# Acoustic_Signal_Localization_Schematic.net
KiCad netlist of a schematic drawn in Altium Designer
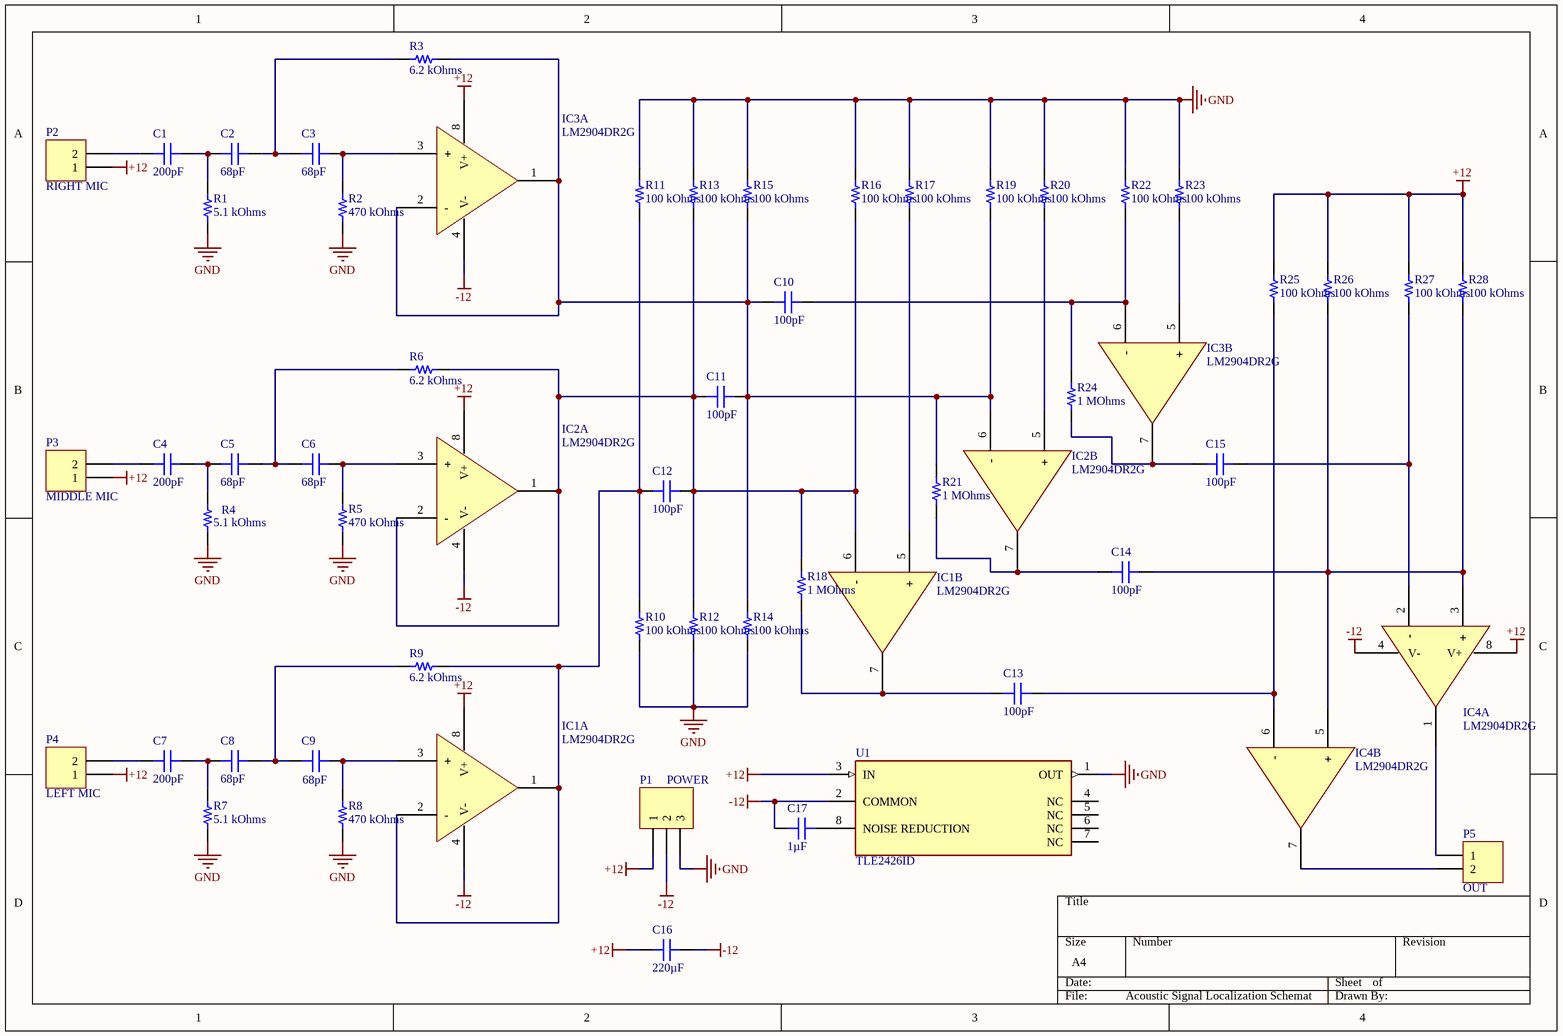
[diagram p0: Acoustic Signal Localization Schematic.SchDoc]

(export (version "E")
  (design (tool "Eeschema 10.0.6"))
  (components
    (comp (ref "C1")
      (value "200pF")
      (footprint "CAP 1210_3225 - 1.6MM")
      (description "CAP CER 1210 200PF 630V C0G 5% F")
      (fields (field (name "PART NUMBER") "C1210X201JBGACAUTO") (field (name "MANUFACTURER") "KEMET"))
      (libsource (lib "Celestial Altium Library - altium_library") (part "Capacitor"))
    )
    (comp (ref "C2")
      (value "68pF")
      (footprint "CAP 1210_3225 - 1.6MM")
      (description "CAP CER 680PF 2KV X7R 1210")
      (fields (field (name "PART NUMBER") "C1210C681KGRACTU") (field (name "MANUFACTURER") "KEMET"))
      (libsource (lib "Celestial Altium Library - altium_library") (part "Capacitor"))
    )
    (comp (ref "C3")
      (value "68pF")
      (footprint "CAP 1210_3225 - 1.6MM")
      (description "CAP CER 680PF 2KV X7R 1210")
      (fields (field (name "PART NUMBER") "C1210C681KGRACTU") (field (name "MANUFACTURER") "KEMET"))
      (libsource (lib "Celestial Altium Library - altium_library") (part "Capacitor"))
    )
    (comp (ref "C4")
      (value "200pF")
      (footprint "CAP 1210_3225 - 1.6MM")
      (description "CAP CER 1210 200PF 630V C0G 5% F")
      (fields (field (name "PART NUMBER") "C1210X201JBGACAUTO") (field (name "MANUFACTURER") "KEMET"))
      (libsource (lib "Celestial Altium Library - altium_library") (part "Capacitor"))
    )
    (comp (ref "C5")
      (value "68pF")
      (footprint "CAP 1210_3225 - 1.6MM")
      (description "CAP CER 680PF 2KV X7R 1210")
      (fields (field (name "PART NUMBER") "C1210C681KGRACTU") (field (name "MANUFACTURER") "KEMET"))
      (libsource (lib "Celestial Altium Library - altium_library") (part "Capacitor"))
    )
    (comp (ref "C6")
      (value "68pF")
      (footprint "CAP 1210_3225 - 1.6MM")
      (description "CAP CER 680PF 2KV X7R 1210")
      (fields (field (name "PART NUMBER") "C1210C681KGRACTU") (field (name "MANUFACTURER") "KEMET"))
      (libsource (lib "Celestial Altium Library - altium_library") (part "Capacitor"))
    )
    (comp (ref "C7")
      (value "200pF")
      (footprint "CAP 1210_3225 - 1.6MM")
      (description "CAP CER 1210 200PF 630V C0G 5% F")
      (fields (field (name "PART NUMBER") "C1210X201JBGACAUTO") (field (name "MANUFACTURER") "KEMET"))
      (libsource (lib "Celestial Altium Library - altium_library") (part "Capacitor"))
    )
    (comp (ref "C8")
      (value "68pF")
      (footprint "CAP 1210_3225 - 1.6MM")
      (description "CAP CER 680PF 2KV X7R 1210")
      (fields (field (name "PART NUMBER") "C1210C681KGRACTU") (field (name "MANUFACTURER") "KEMET"))
      (libsource (lib "Celestial Altium Library - altium_library") (part "Capacitor"))
    )
    (comp (ref "C9")
      (value "68pF")
      (footprint "CAP 1210_3225 - 1.6MM")
      (description "CAP CER 680PF 2KV X7R 1210")
      (fields (field (name "PART NUMBER") "C1210C681KGRACTU") (field (name "MANUFACTURER") "KEMET"))
      (libsource (lib "Celestial Altium Library - altium_library") (part "Capacitor"))
    )
    (comp (ref "C10")
      (value "100pF")
      (footprint "CAP 1210_3225 - 1.8MM")
      (description "CAP CER 100PF 1KV C0G/NP0 1210")
      (fields
        (field (name "PART NUMBER") "VJ1210A101JXGAT5Z")
        (field (name "MANUFACTURER") "Vishay Vitramon")
      )
      (libsource (lib "Celestial Altium Library - altium_library") (part "Capacitor"))
    )
    (comp (ref "C11")
      (value "100pF")
      (footprint "CAP 1210_3225 - 1.8MM")
      (description "CAP CER 100PF 1KV C0G/NP0 1210")
      (fields
        (field (name "PART NUMBER") "VJ1210A101JXGAT5Z")
        (field (name "MANUFACTURER") "Vishay Vitramon")
      )
      (libsource (lib "Celestial Altium Library - altium_library") (part "Capacitor"))
    )
    (comp (ref "C12")
      (value "100pF")
      (footprint "CAP 1210_3225 - 1.8MM")
      (description "CAP CER 100PF 1KV C0G/NP0 1210")
      (fields
        (field (name "PART NUMBER") "VJ1210A101JXGAT5Z")
        (field (name "MANUFACTURER") "Vishay Vitramon")
      )
      (libsource (lib "Celestial Altium Library - altium_library") (part "Capacitor"))
    )
    (comp (ref "C13")
      (value "100pF")
      (footprint "CAP 1210_3225 - 1.8MM")
      (description "CAP CER 100PF 1KV C0G/NP0 1210")
      (fields
        (field (name "PART NUMBER") "VJ1210A101JXGAT5Z")
        (field (name "MANUFACTURER") "Vishay Vitramon")
      )
      (libsource (lib "Celestial Altium Library - altium_library") (part "Capacitor"))
    )
    (comp (ref "C14")
      (value "100pF")
      (footprint "CAP 1210_3225 - 1.8MM")
      (description "CAP CER 100PF 1KV C0G/NP0 1210")
      (fields
        (field (name "PART NUMBER") "VJ1210A101JXGAT5Z")
        (field (name "MANUFACTURER") "Vishay Vitramon")
      )
      (libsource (lib "Celestial Altium Library - altium_library") (part "Capacitor"))
    )
    (comp (ref "C15")
      (value "100pF")
      (footprint "CAP 1210_3225 - 1.8MM")
      (description "CAP CER 100PF 1KV C0G/NP0 1210")
      (fields
        (field (name "PART NUMBER") "VJ1210A101JXGAT5Z")
        (field (name "MANUFACTURER") "Vishay Vitramon")
      )
      (libsource (lib "Celestial Altium Library - altium_library") (part "Capacitor"))
    )
    (comp (ref "C16")
      (value "220µF")
      (footprint "CAP 1210_3225 - 2.8MM")
      (description "CAP CER 220UF 2.5V X6S 1210")
      (fields
        (field (name "PART NUMBER") "GRM32EC80E227ME05L")
        (field (name "MANUFACTURER") "Murata Electronics")
      )
      (libsource (lib "Celestial Altium Library - altium_library") (part "Capacitor"))
    )
    (comp (ref "C17")
      (value "1µF")
      (footprint "CAP 1210_3225 - 2.8MM")
      (description "CAP CER 1UF 100V X7R 1210")
      (fields
        (field (name "PART NUMBER") "CL32B105KCJNNNE")
        (field (name "MANUFACTURER") "Samsung Electro-Mechanics")
      )
      (libsource (lib "Celestial Altium Library - altium_library") (part "Capacitor"))
    )
    (comp (ref "IC1")
      (value "LM2904DR2G")
      (footprint "TI SOIC-8 D")
      (description "IC OPAMP GP 2 CIRCUIT 8SOIC")
      (fields (field (name "MANUFACTURER") "ON Semiconductor"))
      (libsource (lib "Celestial Altium Library - altium_library") (part "TI LM2904DR"))
    )
    (comp (ref "IC2")
      (value "LM2904DR2G")
      (footprint "TI SOIC-8 D")
      (description "IC OPAMP GP 2 CIRCUIT 8SOIC")
      (fields (field (name "MANUFACTURER") "ON Semiconductor"))
      (libsource (lib "Celestial Altium Library - altium_library") (part "TI LM2904DR"))
    )
    (comp (ref "IC3")
      (value "LM2904DR2G")
      (footprint "TI SOIC-8 D")
      (description "IC OPAMP GP 2 CIRCUIT 8SOIC")
      (fields (field (name "MANUFACTURER") "ON Semiconductor"))
      (libsource (lib "Celestial Altium Library - altium_library") (part "TI LM2904DR"))
    )
    (comp (ref "IC4")
      (value "LM2904DR2G")
      (footprint "TI SOIC-8 D")
      (description "IC OPAMP GP 2 CIRCUIT 8SOIC")
      (fields (field (name "MANUFACTURER") "ON Semiconductor"))
      (libsource (lib "Celestial Altium Library - altium_library") (part "TI LM2904DR"))
    )
    (comp (ref "P1")
      (value "POWER")
      (footprint "HDR1X3")
      (description "Header, 3-Pin")
      (fields (field (name "PUBLISHER") "Altium Limited"))
      (libsource (lib "Miscellaneous Connectors") (part "Header 3"))
    )
    (comp (ref "P2")
      (value "RIGHT MIC")
      (footprint "HDR1X2")
      (description "Header, 2-Pin")
      (fields (field (name "PUBLISHER") "Altium Limited"))
      (libsource (lib "") (part "Header 2_1"))
    )
    (comp (ref "P3")
      (value "MIDDLE MIC")
      (footprint "HDR1X2")
      (description "Header, 2-Pin")
      (fields (field (name "PUBLISHER") "Altium Limited"))
      (libsource (lib "") (part "Header 2_1"))
    )
    (comp (ref "P4")
      (value "LEFT MIC")
      (footprint "HDR1X2")
      (description "Header, 2-Pin")
      (fields (field (name "PUBLISHER") "Altium Limited"))
      (libsource (lib "") (part "Header 2_1"))
    )
    (comp (ref "P5")
      (value "OUT")
      (footprint "HDR1X2")
      (description "Header, 2-Pin")
      (fields (field (name "PUBLISHER") "Altium Limited"))
      (libsource (lib "Miscellaneous Connectors") (part "Header 2"))
    )
    (comp (ref "R1")
      (value "5.1 kOhms")
      (footprint "RES 1210_3225")
      (description "RES 5.1K OHM 5% 1/2W 1210")
      (fields
        (field (name "PART NUMBER") "RK73B2ETTD512J")
        (field (name "MANUFACTURER") "KOA Speer Electronics, Inc.")
      )
      (libsource (lib "Celestial Altium Library - altium_library") (part "Resistor"))
    )
    (comp (ref "R2")
      (value "470 kOhms")
      (footprint "RES 1210_3225")
      (description "RES 470K OHM 5% 1/3W 1210")
      (fields
        (field (name "PART NUMBER") "RMCF1210JT470K")
        (field (name "MANUFACTURER") "Stackpole Electronics Inc")
      )
      (libsource (lib "Celestial Altium Library - altium_library") (part "Resistor"))
    )
    (comp (ref "R3")
      (value "6.2 kOhms")
      (footprint "RES 1210_3225")
      (description "RES 6.2K OHM 5% 1/2W 1210")
      (fields
        (field (name "PART NUMBER") "RK73B2ETTD622J")
        (field (name "MANUFACTURER") "KOA Speer Electronics, Inc.")
      )
      (libsource (lib "Celestial Altium Library - altium_library") (part "Resistor"))
    )
    (comp (ref "R4")
      (value "5.1 kOhms")
      (footprint "RES 1210_3225")
      (description "RES 5.1K OHM 5% 1/2W 1210")
      (fields
        (field (name "PART NUMBER") "RK73B2ETTD512J")
        (field (name "MANUFACTURER") "KOA Speer Electronics, Inc.")
      )
      (libsource (lib "Celestial Altium Library - altium_library") (part "Resistor"))
    )
    (comp (ref "R5")
      (value "470 kOhms")
      (footprint "RES 1210_3225")
      (description "RES 470K OHM 5% 1/3W 1210")
      (fields
        (field (name "PART NUMBER") "RMCF1210JT470K")
        (field (name "MANUFACTURER") "Stackpole Electronics Inc")
      )
      (libsource (lib "Celestial Altium Library - altium_library") (part "Resistor"))
    )
    (comp (ref "R6")
      (value "6.2 kOhms")
      (footprint "RES 1210_3225")
      (description "RES 6.2K OHM 5% 1/2W 1210")
      (fields
        (field (name "PART NUMBER") "RK73B2ETTD622J")
        (field (name "MANUFACTURER") "KOA Speer Electronics, Inc.")
      )
      (libsource (lib "Celestial Altium Library - altium_library") (part "Resistor"))
    )
    (comp (ref "R7")
      (value "5.1 kOhms")
      (footprint "RES 1210_3225")
      (description "RES 5.1K OHM 5% 1/2W 1210")
      (fields
        (field (name "PART NUMBER") "RK73B2ETTD512J")
        (field (name "MANUFACTURER") "KOA Speer Electronics, Inc.")
      )
      (libsource (lib "Celestial Altium Library - altium_library") (part "Resistor"))
    )
    (comp (ref "R8")
      (value "470 kOhms")
      (footprint "RES 1210_3225")
      (description "RES 470K OHM 5% 1/3W 1210")
      (fields
        (field (name "PART NUMBER") "RMCF1210JT470K")
        (field (name "MANUFACTURER") "Stackpole Electronics Inc")
      )
      (libsource (lib "Celestial Altium Library - altium_library") (part "Resistor"))
    )
    (comp (ref "R9")
      (value "6.2 kOhms")
      (footprint "RES 1210_3225")
      (description "RES 6.2K OHM 5% 1/2W 1210")
      (fields
        (field (name "PART NUMBER") "RK73B2ETTD622J")
        (field (name "MANUFACTURER") "KOA Speer Electronics, Inc.")
      )
      (libsource (lib "Celestial Altium Library - altium_library") (part "Resistor"))
    )
    (comp (ref "R10")
      (value "100 kOhms")
      (footprint "RES 1210_3225")
      (description "RES 100K OHM 1% 1/3W 1210")
      (fields
        (field (name "PART NUMBER") "RMCF1210FT100K")
        (field (name "MANUFACTURER") "Stackpole Electronics Inc")
      )
      (libsource (lib "Celestial Altium Library - altium_library") (part "Resistor"))
    )
    (comp (ref "R11")
      (value "100 kOhms")
      (footprint "RES 1210_3225")
      (description "RES 100K OHM 1% 1/3W 1210")
      (fields
        (field (name "PART NUMBER") "RMCF1210FT100K")
        (field (name "MANUFACTURER") "Stackpole Electronics Inc")
      )
      (libsource (lib "Celestial Altium Library - altium_library") (part "Resistor"))
    )
    (comp (ref "R12")
      (value "100 kOhms")
      (footprint "RES 1210_3225")
      (description "RES 100K OHM 1% 1/3W 1210")
      (fields
        (field (name "PART NUMBER") "RMCF1210FT100K")
        (field (name "MANUFACTURER") "Stackpole Electronics Inc")
      )
      (libsource (lib "Celestial Altium Library - altium_library") (part "Resistor"))
    )
    (comp (ref "R13")
      (value "100 kOhms")
      (footprint "RES 1210_3225")
      (description "RES 100K OHM 1% 1/3W 1210")
      (fields
        (field (name "PART NUMBER") "RMCF1210FT100K")
        (field (name "MANUFACTURER") "Stackpole Electronics Inc")
      )
      (libsource (lib "Celestial Altium Library - altium_library") (part "Resistor"))
    )
    (comp (ref "R14")
      (value "100 kOhms")
      (footprint "RES 1210_3225")
      (description "RES 100K OHM 1% 1/3W 1210")
      (fields
        (field (name "PART NUMBER") "RMCF1210FT100K")
        (field (name "MANUFACTURER") "Stackpole Electronics Inc")
      )
      (libsource (lib "Celestial Altium Library - altium_library") (part "Resistor"))
    )
    (comp (ref "R15")
      (value "100 kOhms")
      (footprint "RES 1210_3225")
      (description "RES 100K OHM 1% 1/3W 1210")
      (fields
        (field (name "PART NUMBER") "RMCF1210FT100K")
        (field (name "MANUFACTURER") "Stackpole Electronics Inc")
      )
      (libsource (lib "Celestial Altium Library - altium_library") (part "Resistor"))
    )
    (comp (ref "R16")
      (value "100 kOhms")
      (footprint "RES 1210_3225")
      (description "RES 100K OHM 1% 1/3W 1210")
      (fields
        (field (name "PART NUMBER") "RMCF1210FT100K")
        (field (name "MANUFACTURER") "Stackpole Electronics Inc")
      )
      (libsource (lib "Celestial Altium Library - altium_library") (part "Resistor"))
    )
    (comp (ref "R17")
      (value "100 kOhms")
      (footprint "RES 1210_3225")
      (description "RES 100K OHM 1% 1/3W 1210")
      (fields
        (field (name "PART NUMBER") "RMCF1210FT100K")
        (field (name "MANUFACTURER") "Stackpole Electronics Inc")
      )
      (libsource (lib "Celestial Altium Library - altium_library") (part "Resistor"))
    )
    (comp (ref "R18")
      (value "1 MOhms")
      (footprint "RES 1210_3225")
      (description "RES 1M OHM 5% 1/2W 1210")
      (fields
        (field (name "PART NUMBER") "RK73B2ETTD105J")
        (field (name "MANUFACTURER") "KOA Speer Electronics, Inc.")
      )
      (libsource (lib "Celestial Altium Library - altium_library") (part "Resistor"))
    )
    (comp (ref "R19")
      (value "100 kOhms")
      (footprint "RES 1210_3225")
      (description "RES 100K OHM 1% 1/3W 1210")
      (fields
        (field (name "PART NUMBER") "RMCF1210FT100K")
        (field (name "MANUFACTURER") "Stackpole Electronics Inc")
      )
      (libsource (lib "Celestial Altium Library - altium_library") (part "Resistor"))
    )
    (comp (ref "R20")
      (value "100 kOhms")
      (footprint "RES 1210_3225")
      (description "RES 100K OHM 1% 1/3W 1210")
      (fields
        (field (name "PART NUMBER") "RMCF1210FT100K")
        (field (name "MANUFACTURER") "Stackpole Electronics Inc")
      )
      (libsource (lib "Celestial Altium Library - altium_library") (part "Resistor"))
    )
    (comp (ref "R21")
      (value "1 MOhms")
      (footprint "RES 1210_3225")
      (description "RES 1M OHM 5% 1/2W 1210")
      (fields
        (field (name "PART NUMBER") "RK73B2ETTD105J")
        (field (name "MANUFACTURER") "KOA Speer Electronics, Inc.")
      )
      (libsource (lib "Celestial Altium Library - altium_library") (part "Resistor"))
    )
    (comp (ref "R22")
      (value "100 kOhms")
      (footprint "RES 1210_3225")
      (description "RES 100K OHM 1% 1/3W 1210")
      (fields
        (field (name "PART NUMBER") "RMCF1210FT100K")
        (field (name "MANUFACTURER") "Stackpole Electronics Inc")
      )
      (libsource (lib "Celestial Altium Library - altium_library") (part "Resistor"))
    )
    (comp (ref "R23")
      (value "100 kOhms")
      (footprint "RES 1210_3225")
      (description "RES 100K OHM 1% 1/3W 1210")
      (fields
        (field (name "PART NUMBER") "RMCF1210FT100K")
        (field (name "MANUFACTURER") "Stackpole Electronics Inc")
      )
      (libsource (lib "Celestial Altium Library - altium_library") (part "Resistor"))
    )
    (comp (ref "R24")
      (value "1 MOhms")
      (footprint "RES 1210_3225")
      (description "RES 1M OHM 5% 1/2W 1210")
      (fields
        (field (name "PART NUMBER") "RK73B2ETTD105J")
        (field (name "MANUFACTURER") "KOA Speer Electronics, Inc.")
      )
      (libsource (lib "Celestial Altium Library - altium_library") (part "Resistor"))
    )
    (comp (ref "R25")
      (value "100 kOhms")
      (footprint "RES 1210_3225")
      (description "RES 100K OHM 1% 1/3W 1210")
      (fields
        (field (name "PART NUMBER") "RMCF1210FT100K")
        (field (name "MANUFACTURER") "Stackpole Electronics Inc")
      )
      (libsource (lib "Celestial Altium Library - altium_library") (part "Resistor"))
    )
    (comp (ref "R26")
      (value "100 kOhms")
      (footprint "RES 1210_3225")
      (description "RES 100K OHM 1% 1/3W 1210")
      (fields
        (field (name "PART NUMBER") "RMCF1210FT100K")
        (field (name "MANUFACTURER") "Stackpole Electronics Inc")
      )
      (libsource (lib "Celestial Altium Library - altium_library") (part "Resistor"))
    )
    (comp (ref "R27")
      (value "100 kOhms")
      (footprint "RES 1210_3225")
      (description "RES 100K OHM 1% 1/3W 1210")
      (fields
        (field (name "PART NUMBER") "RMCF1210FT100K")
        (field (name "MANUFACTURER") "Stackpole Electronics Inc")
      )
      (libsource (lib "Celestial Altium Library - altium_library") (part "Resistor"))
    )
    (comp (ref "R28")
      (value "100 kOhms")
      (footprint "RES 1210_3225")
      (description "RES 100K OHM 1% 1/3W 1210")
      (fields
        (field (name "PART NUMBER") "RMCF1210FT100K")
        (field (name "MANUFACTURER") "Stackpole Electronics Inc")
      )
      (libsource (lib "Celestial Altium Library - altium_library") (part "Resistor"))
    )
    (comp (ref "U1")
      (value "TLE2426ID")
      (footprint "FP-D0008A-IPC_B")
      (description "IC VREF GND REF 20V 1% 8SOIC")
      (fields (field (name "TOLERANCE") "1%"))
      (libsource (lib "Altium Content Vault") (part "e6df97921648a47b25dc48aad81dd64"))
    )
  )
  (nets
    (net (code "1") (name "+12") (class "Default")
      (node (ref "C16") (pin "1") (pinfunction "1_1") (pintype "passive"))
      (node (ref "IC1") (pin "8") (pinfunction "V+_8") (pintype "passive"))
      (node (ref "IC2") (pin "8") (pinfunction "V+_8") (pintype "passive"))
      (node (ref "IC3") (pin "8") (pinfunction "V+_8") (pintype "passive"))
      (node (ref "IC4") (pin "8") (pinfunction "V+_8") (pintype "passive"))
      (node (ref "P1") (pin "1") (pinfunction "1_1") (pintype "passive"))
      (node (ref "P2") (pin "1") (pinfunction "1_1") (pintype "passive"))
      (node (ref "P3") (pin "1") (pinfunction "1_1") (pintype "passive"))
      (node (ref "P4") (pin "1") (pinfunction "1_1") (pintype "passive"))
      (node (ref "R25") (pin "2") (pinfunction "2_2") (pintype "passive"))
      (node (ref "R26") (pin "2") (pinfunction "2_2") (pintype "passive"))
      (node (ref "R27") (pin "2") (pinfunction "2_2") (pintype "passive"))
      (node (ref "R28") (pin "2") (pinfunction "2_2") (pintype "passive"))
      (node (ref "U1") (pin "3") (pinfunction "IN_3") (pintype "input"))
    )
    (net (code "2") (name "-12") (class "Default")
      (node (ref "C16") (pin "2") (pinfunction "2_2") (pintype "passive"))
      (node (ref "C17") (pin "1") (pinfunction "1_1") (pintype "passive"))
      (node (ref "IC1") (pin "4") (pinfunction "V-_4") (pintype "passive"))
      (node (ref "IC2") (pin "4") (pinfunction "V-_4") (pintype "passive"))
      (node (ref "IC3") (pin "4") (pinfunction "V-_4") (pintype "passive"))
      (node (ref "IC4") (pin "4") (pinfunction "V-_4") (pintype "passive"))
      (node (ref "P1") (pin "2") (pinfunction "2_2") (pintype "passive"))
      (node (ref "U1") (pin "2") (pinfunction "COMMON_2") (pintype "passive"))
    )
    (net (code "3") (name "GND") (class "Default")
      (node (ref "P1") (pin "3") (pinfunction "3_3") (pintype "passive"))
      (node (ref "R1") (pin "1") (pinfunction "1_1") (pintype "passive"))
      (node (ref "R10") (pin "1") (pinfunction "1_1") (pintype "passive"))
      (node (ref "R11") (pin "2") (pinfunction "2_2") (pintype "passive"))
      (node (ref "R12") (pin "1") (pinfunction "1_1") (pintype "passive"))
      (node (ref "R13") (pin "2") (pinfunction "2_2") (pintype "passive"))
      (node (ref "R14") (pin "1") (pinfunction "1_1") (pintype "passive"))
      (node (ref "R15") (pin "2") (pinfunction "2_2") (pintype "passive"))
      (node (ref "R16") (pin "2") (pinfunction "2_2") (pintype "passive"))
      (node (ref "R17") (pin "2") (pinfunction "2_2") (pintype "passive"))
      (node (ref "R19") (pin "2") (pinfunction "2_2") (pintype "passive"))
      (node (ref "R2") (pin "1") (pinfunction "1_1") (pintype "passive"))
      (node (ref "R20") (pin "2") (pinfunction "2_2") (pintype "passive"))
      (node (ref "R22") (pin "2") (pinfunction "2_2") (pintype "passive"))
      (node (ref "R23") (pin "2") (pinfunction "2_2") (pintype "passive"))
      (node (ref "R4") (pin "1") (pinfunction "1_1") (pintype "passive"))
      (node (ref "R5") (pin "1") (pinfunction "1_1") (pintype "passive"))
      (node (ref "R7") (pin "1") (pinfunction "1_1") (pintype "passive"))
      (node (ref "R8") (pin "1") (pinfunction "1_1") (pintype "passive"))
      (node (ref "U1") (pin "1") (pinfunction "OUT_1") (pintype "output"))
    )
    (net (code "4") (name "Net-(C1-Pad1)") (class "Default")
      (node (ref "C1") (pin "1") (pinfunction "1_1") (pintype "passive"))
      (node (ref "P2") (pin "2") (pinfunction "2_2") (pintype "passive"))
    )
    (net (code "5") (name "Net-(C1-Pad2)") (class "Default")
      (node (ref "C1") (pin "2") (pinfunction "2_2") (pintype "passive"))
      (node (ref "C2") (pin "1") (pinfunction "1_1") (pintype "passive"))
      (node (ref "R1") (pin "2") (pinfunction "2_2") (pintype "passive"))
    )
    (net (code "6") (name "Net-(C2-Pad2)") (class "Default")
      (node (ref "C2") (pin "2") (pinfunction "2_2") (pintype "passive"))
      (node (ref "C3") (pin "1") (pinfunction "1_1") (pintype "passive"))
      (node (ref "R3") (pin "2") (pinfunction "2_2") (pintype "passive"))
    )
    (net (code "7") (name "Net-(C4-Pad1)") (class "Default")
      (node (ref "C4") (pin "1") (pinfunction "1_1") (pintype "passive"))
      (node (ref "P3") (pin "2") (pinfunction "2_2") (pintype "passive"))
    )
    (net (code "8") (name "Net-(C4-Pad2)") (class "Default")
      (node (ref "C4") (pin "2") (pinfunction "2_2") (pintype "passive"))
      (node (ref "C5") (pin "1") (pinfunction "1_1") (pintype "passive"))
      (node (ref "R4") (pin "2") (pinfunction "2_2") (pintype "passive"))
    )
    (net (code "9") (name "Net-(C5-Pad2)") (class "Default")
      (node (ref "C5") (pin "2") (pinfunction "2_2") (pintype "passive"))
      (node (ref "C6") (pin "1") (pinfunction "1_1") (pintype "passive"))
      (node (ref "R6") (pin "2") (pinfunction "2_2") (pintype "passive"))
    )
    (net (code "10") (name "Net-(C7-Pad1)") (class "Default")
      (node (ref "C7") (pin "1") (pinfunction "1_1") (pintype "passive"))
      (node (ref "P4") (pin "2") (pinfunction "2_2") (pintype "passive"))
    )
    (net (code "11") (name "Net-(C7-Pad2)") (class "Default")
      (node (ref "C7") (pin "2") (pinfunction "2_2") (pintype "passive"))
      (node (ref "C8") (pin "1") (pinfunction "1_1") (pintype "passive"))
      (node (ref "R7") (pin "2") (pinfunction "2_2") (pintype "passive"))
    )
    (net (code "12") (name "Net-(C8-Pad2)") (class "Default")
      (node (ref "C8") (pin "2") (pinfunction "2_2") (pintype "passive"))
      (node (ref "C9") (pin "1") (pinfunction "1_1") (pintype "passive"))
      (node (ref "R9") (pin "2") (pinfunction "2_2") (pintype "passive"))
    )
    (net (code "13") (name "Net-(IC1A-+)") (class "Default")
      (node (ref "C9") (pin "2") (pinfunction "2_2") (pintype "passive"))
      (node (ref "IC1") (pin "3") (pinfunction "+_3") (pintype "passive"))
      (node (ref "R8") (pin "2") (pinfunction "2_2") (pintype "passive"))
    )
    (net (code "14") (name "Net-(IC1A--)") (class "Default")
      (node (ref "C12") (pin "1") (pinfunction "1_1") (pintype "passive"))
      (node (ref "IC1") (pin "1") (pinfunction "OUTA_1") (pintype "passive"))
      (node (ref "IC1") (pin "2") (pinfunction "-_2") (pintype "passive"))
      (node (ref "R10") (pin "2") (pinfunction "2_2") (pintype "passive"))
      (node (ref "R11") (pin "1") (pinfunction "1_1") (pintype "passive"))
      (node (ref "R9") (pin "1") (pinfunction "1_1") (pintype "passive"))
    )
    (net (code "15") (name "Net-(IC1B-+)") (class "Default")
      (node (ref "IC1") (pin "5") (pinfunction "+_5") (pintype "passive"))
      (node (ref "R17") (pin "1") (pinfunction "1_1") (pintype "passive"))
    )
    (net (code "16") (name "Net-(IC1B--)") (class "Default")
      (node (ref "C11") (pin "1") (pinfunction "1_1") (pintype "passive"))
      (node (ref "C12") (pin "2") (pinfunction "2_2") (pintype "passive"))
      (node (ref "IC1") (pin "6") (pinfunction "-_6") (pintype "passive"))
      (node (ref "IC2") (pin "1") (pinfunction "OUTA_1") (pintype "passive"))
      (node (ref "IC2") (pin "2") (pinfunction "-_2") (pintype "passive"))
      (node (ref "R12") (pin "2") (pinfunction "2_2") (pintype "passive"))
      (node (ref "R13") (pin "1") (pinfunction "1_1") (pintype "passive"))
      (node (ref "R16") (pin "1") (pinfunction "1_1") (pintype "passive"))
      (node (ref "R18") (pin "2") (pinfunction "2_2") (pintype "passive"))
      (node (ref "R6") (pin "1") (pinfunction "1_1") (pintype "passive"))
    )
    (net (code "17") (name "Net-(IC1B-OUTB)") (class "Default")
      (node (ref "C13") (pin "1") (pinfunction "1_1") (pintype "passive"))
      (node (ref "IC1") (pin "7") (pinfunction "OUTB_7") (pintype "passive"))
      (node (ref "R18") (pin "1") (pinfunction "1_1") (pintype "passive"))
    )
    (net (code "18") (name "Net-(IC2A-+)") (class "Default")
      (node (ref "C6") (pin "2") (pinfunction "2_2") (pintype "passive"))
      (node (ref "IC2") (pin "3") (pinfunction "+_3") (pintype "passive"))
      (node (ref "R5") (pin "2") (pinfunction "2_2") (pintype "passive"))
    )
    (net (code "19") (name "Net-(IC2B-+)") (class "Default")
      (node (ref "IC2") (pin "5") (pinfunction "+_5") (pintype "passive"))
      (node (ref "R20") (pin "1") (pinfunction "1_1") (pintype "passive"))
    )
    (net (code "20") (name "Net-(IC2B--)") (class "Default")
      (node (ref "C10") (pin "1") (pinfunction "1_1") (pintype "passive"))
      (node (ref "C11") (pin "2") (pinfunction "2_2") (pintype "passive"))
      (node (ref "IC2") (pin "6") (pinfunction "-_6") (pintype "passive"))
      (node (ref "IC3") (pin "1") (pinfunction "OUTA_1") (pintype "passive"))
      (node (ref "IC3") (pin "2") (pinfunction "-_2") (pintype "passive"))
      (node (ref "R14") (pin "2") (pinfunction "2_2") (pintype "passive"))
      (node (ref "R15") (pin "1") (pinfunction "1_1") (pintype "passive"))
      (node (ref "R19") (pin "1") (pinfunction "1_1") (pintype "passive"))
      (node (ref "R21") (pin "2") (pinfunction "2_2") (pintype "passive"))
      (node (ref "R3") (pin "1") (pinfunction "1_1") (pintype "passive"))
    )
    (net (code "21") (name "Net-(IC2B-OUTB)") (class "Default")
      (node (ref "C14") (pin "1") (pinfunction "1_1") (pintype "passive"))
      (node (ref "IC2") (pin "7") (pinfunction "OUTB_7") (pintype "passive"))
      (node (ref "R21") (pin "1") (pinfunction "1_1") (pintype "passive"))
    )
    (net (code "22") (name "Net-(IC3A-+)") (class "Default")
      (node (ref "C3") (pin "2") (pinfunction "2_2") (pintype "passive"))
      (node (ref "IC3") (pin "3") (pinfunction "+_3") (pintype "passive"))
      (node (ref "R2") (pin "2") (pinfunction "2_2") (pintype "passive"))
    )
    (net (code "23") (name "Net-(IC3B-+)") (class "Default")
      (node (ref "IC3") (pin "5") (pinfunction "+_5") (pintype "passive"))
      (node (ref "R23") (pin "1") (pinfunction "1_1") (pintype "passive"))
    )
    (net (code "24") (name "Net-(IC3B--)") (class "Default")
      (node (ref "C10") (pin "2") (pinfunction "2_2") (pintype "passive"))
      (node (ref "IC3") (pin "6") (pinfunction "-_6") (pintype "passive"))
      (node (ref "R22") (pin "1") (pinfunction "1_1") (pintype "passive"))
      (node (ref "R24") (pin "2") (pinfunction "2_2") (pintype "passive"))
    )
    (net (code "25") (name "Net-(IC3B-OUTB)") (class "Default")
      (node (ref "C15") (pin "1") (pinfunction "1_1") (pintype "passive"))
      (node (ref "IC3") (pin "7") (pinfunction "OUTB_7") (pintype "passive"))
      (node (ref "R24") (pin "1") (pinfunction "1_1") (pintype "passive"))
    )
    (net (code "26") (name "Net-(IC4A-+)") (class "Default")
      (node (ref "C14") (pin "2") (pinfunction "2_2") (pintype "passive"))
      (node (ref "IC4") (pin "3") (pinfunction "+_3") (pintype "passive"))
      (node (ref "IC4") (pin "5") (pinfunction "+_5") (pintype "passive"))
      (node (ref "R26") (pin "1") (pinfunction "1_1") (pintype "passive"))
      (node (ref "R28") (pin "1") (pinfunction "1_1") (pintype "passive"))
    )
    (net (code "27") (name "Net-(IC4A--)") (class "Default")
      (node (ref "C15") (pin "2") (pinfunction "2_2") (pintype "passive"))
      (node (ref "IC4") (pin "2") (pinfunction "-_2") (pintype "passive"))
      (node (ref "R27") (pin "1") (pinfunction "1_1") (pintype "passive"))
    )
    (net (code "28") (name "Net-(IC4A-OUTA)") (class "Default")
      (node (ref "IC4") (pin "1") (pinfunction "OUTA_1") (pintype "passive"))
      (node (ref "P5") (pin "1") (pinfunction "1_1") (pintype "passive"))
    )
    (net (code "29") (name "Net-(IC4B--)") (class "Default")
      (node (ref "C13") (pin "2") (pinfunction "2_2") (pintype "passive"))
      (node (ref "IC4") (pin "6") (pinfunction "-_6") (pintype "passive"))
      (node (ref "R25") (pin "1") (pinfunction "1_1") (pintype "passive"))
    )
    (net (code "30") (name "Net-(IC4B-OUTB)") (class "Default")
      (node (ref "IC4") (pin "7") (pinfunction "OUTB_7") (pintype "passive"))
      (node (ref "P5") (pin "2") (pinfunction "2_2") (pintype "passive"))
    )
    (net (code "31") (name "Net-(U1-NOISE_REDUCTION)") (class "Default")
      (node (ref "C17") (pin "2") (pinfunction "2_2") (pintype "passive"))
      (node (ref "U1") (pin "8") (pinfunction "NOISE_REDUCTION_8") (pintype "passive"))
    )
    (net (code "32") (name "unconnected-(U1-NC-Pad4)") (class "Default")
      (node (ref "U1") (pin "4") (pinfunction "NC_4") (pintype "passive"))
    )
    (net (code "33") (name "unconnected-(U1-NC-Pad5)") (class "Default")
      (node (ref "U1") (pin "5") (pinfunction "NC_5") (pintype "passive"))
    )
    (net (code "34") (name "unconnected-(U1-NC-Pad6)") (class "Default")
      (node (ref "U1") (pin "6") (pinfunction "NC_6") (pintype "passive"))
    )
    (net (code "35") (name "unconnected-(U1-NC-Pad7)") (class "Default")
      (node (ref "U1") (pin "7") (pinfunction "NC_7") (pintype "passive"))
    )
  )
)
